# espduino-12-2.net
KiCad netlist of a schematic drawn in EAGLE
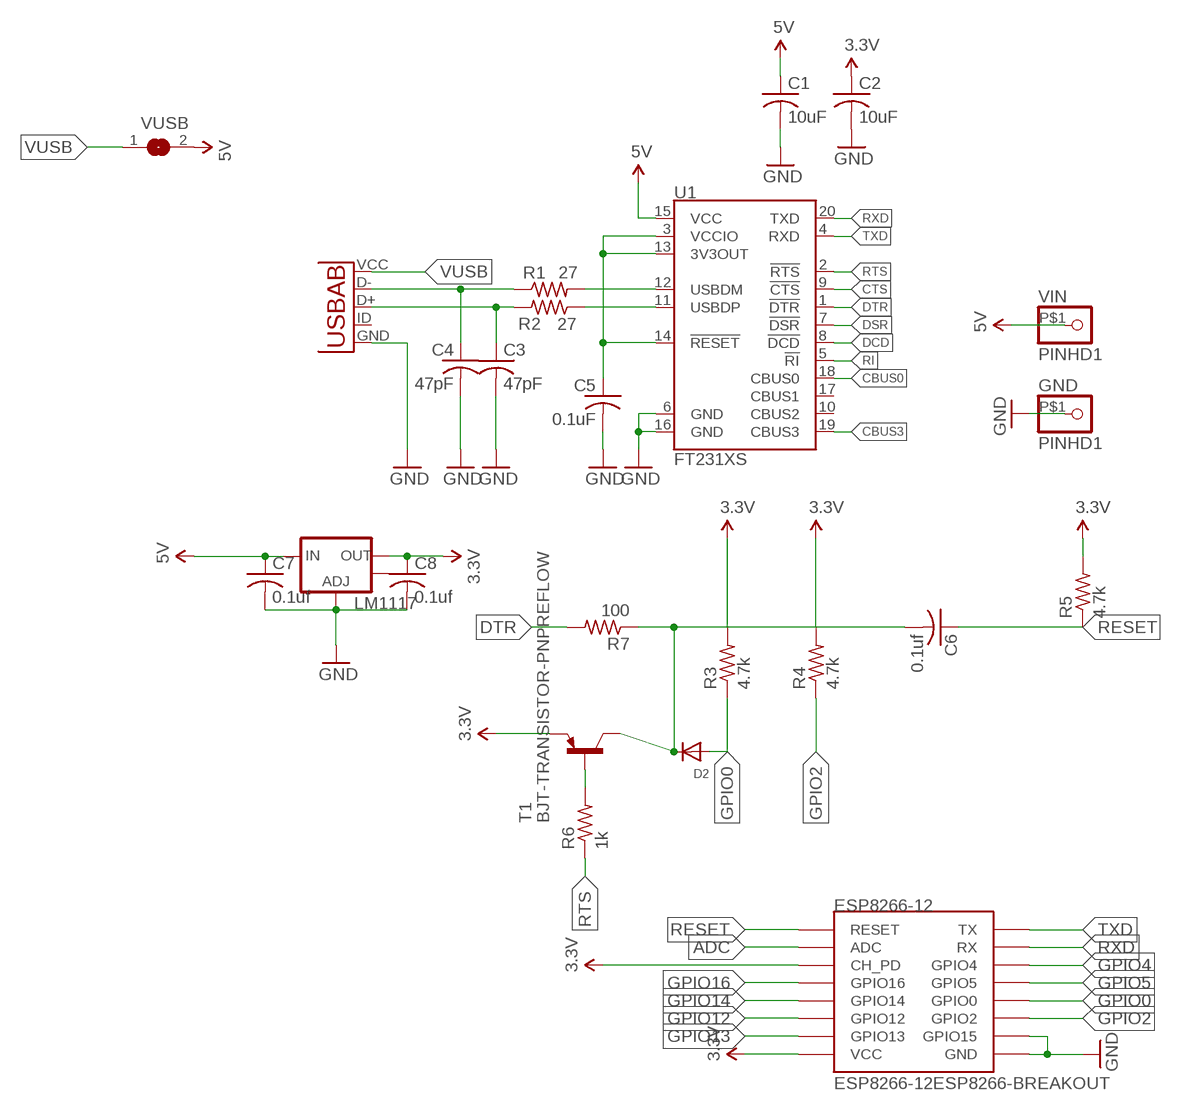
[diagram p0: schematic, sheet 1]

(export (version "E")
  (design (tool "Eeschema 10.0.6"))
  (components
    (comp (ref "C1")
      (value "10uF")
      (footprint "eagle-import:C0603")
      (libsource (lib "eagle-import") (part "C-USC0603"))
    )
    (comp (ref "C2")
      (value "10uF")
      (footprint "eagle-import:C0603")
      (libsource (lib "eagle-import") (part "C-USC0603"))
    )
    (comp (ref "C3")
      (value "47pF")
      (footprint "eagle-import:C0603")
      (libsource (lib "eagle-import") (part "C-USC0603"))
    )
    (comp (ref "C4")
      (value "47pF")
      (footprint "eagle-import:C0603")
      (libsource (lib "eagle-import") (part "C-USC0603"))
    )
    (comp (ref "C5")
      (value "0.1uF")
      (footprint "eagle-import:C0603")
      (libsource (lib "eagle-import") (part "C-USC0603"))
    )
    (comp (ref "C6")
      (value "0.1uf")
      (footprint "eagle-import:C0603")
      (libsource (lib "eagle-import") (part "C-USC0603"))
    )
    (comp (ref "C7")
      (value "0.1uf")
      (footprint "eagle-import:C0603")
      (libsource (lib "eagle-import") (part "C-USC0603"))
    )
    (comp (ref "C8")
      (value "0.1uf")
      (footprint "eagle-import:C0603")
      (libsource (lib "eagle-import") (part "C-USC0603"))
    )
    (comp (ref "D2")
      (value "DIODESOT23_REFLOW")
      (footprint "eagle-import:SOT23-R")
      (libsource (lib "eagle-import") (part "DIODESOT23_REFLOW"))
    )
    (comp (ref "ESP8266-12")
      (value "ESP8266-12ESP8266-BREAKOUT")
      (footprint "eagle-import:ESP8266-12-EXT-HEADERS")
      (libsource (lib "eagle-import") (part "ESP8266-12ESP8266-BREAKOUT"))
    )
    (comp (ref "GND")
      (value "PINHD1")
      (footprint "eagle-import:PINHD1")
      (libsource (lib "eagle-import") (part "PINHD1"))
    )
    (comp (ref "LM1117")
      (value "V_REG_LM1117SOT223")
      (footprint "eagle-import:SOT223")
      (libsource (lib "eagle-import") (part "V_REG_LM1117SOT223"))
    )
    (comp (ref "R1")
      (value "27")
      (footprint "eagle-import:R0603")
      (libsource (lib "eagle-import") (part "R-US_R0603"))
    )
    (comp (ref "R2")
      (value "27")
      (footprint "eagle-import:R0603")
      (libsource (lib "eagle-import") (part "R-US_R0603"))
    )
    (comp (ref "R3")
      (value "4.7k")
      (footprint "eagle-import:R0603")
      (libsource (lib "eagle-import") (part "R-US_R0603"))
    )
    (comp (ref "R4")
      (value "4.7k")
      (footprint "eagle-import:R0603")
      (libsource (lib "eagle-import") (part "R-US_R0603"))
    )
    (comp (ref "R5")
      (value "4.7k")
      (footprint "eagle-import:R0603")
      (libsource (lib "eagle-import") (part "R-US_R0603"))
    )
    (comp (ref "R6")
      (value "1k")
      (footprint "eagle-import:R0603")
      (libsource (lib "eagle-import") (part "R-US_R0603"))
    )
    (comp (ref "R7")
      (value "100")
      (footprint "eagle-import:R0603")
      (libsource (lib "eagle-import") (part "R-US_R0603"))
    )
    (comp (ref "T1")
      (value "BJT-TRANSISTOR-PNPREFLOW")
      (footprint "eagle-import:SOT23-R")
      (libsource (lib "eagle-import") (part "BJT-TRANSISTOR-PNPREFLOW"))
    )
    (comp (ref "U1")
      (value "FT231XS")
      (footprint "eagle-import:SSOP20_L")
      (libsource (lib "eagle-import") (part "FT231XS"))
    )
    (comp (ref "U2")
      (value "USB-AB")
      (footprint "eagle-import:MICRO-USB-A01SB141B1")
      (libsource (lib "eagle-import") (part "USB-AB"))
    )
    (comp (ref "VIN")
      (value "PINHD1")
      (footprint "eagle-import:PINHD1")
      (libsource (lib "eagle-import") (part "PINHD1"))
    )
    (comp (ref "VUSB")
      (value "SJCUTTABLE")
      (footprint "eagle-import:SJ-CUTTABLE")
      (libsource (lib "eagle-import") (part "SJCUTTABLE"))
    )
  )
  (nets
    (net (code "1") (name "3.3V") (class "Default")
      (node (ref "C2") (pin "1") (pinfunction "1_1") (pintype "passive"))
      (node (ref "C8") (pin "1") (pinfunction "1_1") (pintype "passive"))
      (node (ref "ESP8266-12") (pin "CH_PD") (pinfunction "CH_PD_CH_PD") (pintype "bidirectional"))
      (node (ref "ESP8266-12") (pin "VCC") (pinfunction "VCC_VCC") (pintype "bidirectional"))
      (node (ref "ESP8266-12") (pin "VCC_P") (pinfunction "VCC_VCC_P") (pintype "bidirectional"))
      (node (ref "LM1117") (pin "2") (pinfunction "OUT_2") (pintype "output"))
      (node (ref "R3") (pin "2") (pinfunction "2_2") (pintype "passive"))
      (node (ref "R4") (pin "2") (pinfunction "2_2") (pintype "passive"))
      (node (ref "R5") (pin "2") (pinfunction "2_2") (pintype "passive"))
      (node (ref "T1") (pin "2") (pinfunction "E_2") (pintype "passive"))
    )
    (net (code "2") (name "5V") (class "Default")
      (node (ref "C1") (pin "1") (pinfunction "1_1") (pintype "passive"))
      (node (ref "C7") (pin "1") (pinfunction "1_1") (pintype "passive"))
      (node (ref "LM1117") (pin "3") (pinfunction "IN_3") (pintype "input"))
      (node (ref "U1") (pin "15") (pinfunction "VCC_15") (pintype "bidirectional"))
      (node (ref "VIN") (pin "P$1") (pinfunction "GND_P$1") (pintype "passive"))
      (node (ref "VUSB") (pin "2") (pinfunction "2_2") (pintype "passive"))
    )
    (net (code "3") (name "ADC") (class "Default")
      (node (ref "ESP8266-12") (pin "ADC") (pinfunction "ADC_ADC") (pintype "bidirectional"))
      (node (ref "ESP8266-12") (pin "ADC_P") (pinfunction "ADC_ADC_P") (pintype "bidirectional"))
    )
    (net (code "4") (name "CBUS0") (class "Default")
      (node (ref "U1") (pin "18") (pinfunction "CBUS0_18") (pintype "bidirectional"))
    )
    (net (code "5") (name "CBUS3") (class "Default")
      (node (ref "U1") (pin "19") (pinfunction "CBUS3_19") (pintype "bidirectional"))
    )
    (net (code "6") (name "CTS") (class "Default")
      (node (ref "U1") (pin "9") (pinfunction "~{CTS}_9") (pintype "bidirectional"))
    )
    (net (code "7") (name "DCD") (class "Default")
      (node (ref "U1") (pin "8") (pinfunction "~{DCD}_8") (pintype "bidirectional"))
    )
    (net (code "8") (name "DSR") (class "Default")
      (node (ref "U1") (pin "7") (pinfunction "~{DSR}_7") (pintype "bidirectional"))
    )
    (net (code "9") (name "DTR") (class "Default")
      (node (ref "R7") (pin "2") (pinfunction "2_2") (pintype "passive"))
      (node (ref "U1") (pin "1") (pinfunction "~{DTR}_1") (pintype "bidirectional"))
    )
    (net (code "10") (name "GND") (class "Default")
      (node (ref "C1") (pin "2") (pinfunction "2_2") (pintype "passive"))
      (node (ref "C2") (pin "2") (pinfunction "2_2") (pintype "passive"))
      (node (ref "C3") (pin "2") (pinfunction "2_2") (pintype "passive"))
      (node (ref "C4") (pin "2") (pinfunction "2_2") (pintype "passive"))
      (node (ref "C5") (pin "2") (pinfunction "2_2") (pintype "passive"))
      (node (ref "C7") (pin "2") (pinfunction "2_2") (pintype "passive"))
      (node (ref "C8") (pin "2") (pinfunction "2_2") (pintype "passive"))
      (node (ref "ESP8266-12") (pin "GND") (pinfunction "GND_GND") (pintype "bidirectional"))
      (node (ref "ESP8266-12") (pin "GND_P") (pinfunction "GND_GND_P") (pintype "bidirectional"))
      (node (ref "ESP8266-12") (pin "GPIO15") (pinfunction "GPIO15_GPIO15") (pintype "bidirectional"))
      (node (ref "GND") (pin "P$1") (pinfunction "GND_P$1") (pintype "passive"))
      (node (ref "LM1117") (pin "1") (pinfunction "ADJ_1") (pintype "input"))
      (node (ref "U1") (pin "16") (pinfunction "GND_16") (pintype "bidirectional"))
      (node (ref "U1") (pin "6") (pinfunction "GND_6") (pintype "bidirectional"))
      (node (ref "U2") (pin "GND") (pinfunction "GND_GND") (pintype "bidirectional"))
    )
    (net (code "11") (name "GPIO0") (class "Default")
      (node (ref "D2") (pin "1") (pinfunction "A_1") (pintype "passive"))
      (node (ref "ESP8266-12") (pin "GPIO0") (pinfunction "GPIO0_GPIO0") (pintype "bidirectional"))
      (node (ref "ESP8266-12") (pin "GPIO0_P") (pinfunction "GPIO0_GPIO0_P") (pintype "bidirectional"))
      (node (ref "R3") (pin "1") (pinfunction "1_1") (pintype "passive"))
    )
    (net (code "12") (name "GPIO2") (class "Default")
      (node (ref "ESP8266-12") (pin "GPIO2") (pinfunction "GPIO2_GPIO2") (pintype "bidirectional"))
      (node (ref "ESP8266-12") (pin "GPIO2_P") (pinfunction "GPIO2_GPIO2_P") (pintype "bidirectional"))
      (node (ref "R4") (pin "1") (pinfunction "1_1") (pintype "passive"))
    )
    (net (code "13") (name "GPIO4") (class "Default")
      (node (ref "ESP8266-12") (pin "GPIO4") (pinfunction "GPIO4_GPIO4") (pintype "bidirectional"))
      (node (ref "ESP8266-12") (pin "GPIO4_P") (pinfunction "GPIO4_GPIO4_P") (pintype "bidirectional"))
    )
    (net (code "14") (name "GPIO5") (class "Default")
      (node (ref "ESP8266-12") (pin "GPIO5") (pinfunction "GPIO5_GPIO5") (pintype "bidirectional"))
      (node (ref "ESP8266-12") (pin "GPIO5_P") (pinfunction "GPIO5_GPIO5_P") (pintype "bidirectional"))
    )
    (net (code "15") (name "GPIO12") (class "Default")
      (node (ref "ESP8266-12") (pin "GPIO12") (pinfunction "GPIO12_GPIO12") (pintype "bidirectional"))
      (node (ref "ESP8266-12") (pin "GPIO12_P") (pinfunction "GPIO12_GPIO12_P") (pintype "bidirectional"))
    )
    (net (code "16") (name "GPIO13") (class "Default")
      (node (ref "ESP8266-12") (pin "GPIO13") (pinfunction "GPIO13_GPIO13") (pintype "bidirectional"))
      (node (ref "ESP8266-12") (pin "GPIO13_P") (pinfunction "GPIO13_GPIO13_P") (pintype "bidirectional"))
    )
    (net (code "17") (name "GPIO14") (class "Default")
      (node (ref "ESP8266-12") (pin "GPIO14") (pinfunction "GPIO14_GPIO14") (pintype "bidirectional"))
      (node (ref "ESP8266-12") (pin "GPIO14_P") (pinfunction "GPIO14_GPIO14_P") (pintype "bidirectional"))
    )
    (net (code "18") (name "GPIO16") (class "Default")
      (node (ref "ESP8266-12") (pin "GPIO16") (pinfunction "GPIO16_GPIO16") (pintype "bidirectional"))
      (node (ref "ESP8266-12") (pin "GPIO_16_P") (pinfunction "GPIO16_GPIO_16_P") (pintype "bidirectional"))
    )
    (net (code "19") (name "Net-(C3-Pad1)") (class "Default")
      (node (ref "C3") (pin "1") (pinfunction "1_1") (pintype "passive"))
      (node (ref "R2") (pin "2") (pinfunction "2_2") (pintype "passive"))
      (node (ref "U2") (pin "D+") (pinfunction "D+_D+") (pintype "bidirectional"))
    )
    (net (code "20") (name "Net-(C4-Pad1)") (class "Default")
      (node (ref "C4") (pin "1") (pinfunction "1_1") (pintype "passive"))
      (node (ref "R1") (pin "1") (pinfunction "1_1") (pintype "passive"))
      (node (ref "U2") (pin "D-") (pinfunction "D-_D-") (pintype "bidirectional"))
    )
    (net (code "21") (name "Net-(D2-C)") (class "Default")
      (node (ref "C6") (pin "2") (pinfunction "2_2") (pintype "passive"))
      (node (ref "D2") (pin "3") (pinfunction "C_3") (pintype "passive"))
      (node (ref "R7") (pin "1") (pinfunction "1_1") (pintype "passive"))
      (node (ref "T1") (pin "3") (pinfunction "C_3") (pintype "passive"))
    )
    (net (code "22") (name "Net-(T1-B)") (class "Default")
      (node (ref "R6") (pin "2") (pinfunction "2_2") (pintype "passive"))
      (node (ref "T1") (pin "1") (pinfunction "B_1") (pintype "passive"))
    )
    (net (code "23") (name "Net-(U1-3V3OUT)") (class "Default")
      (node (ref "C5") (pin "1") (pinfunction "1_1") (pintype "passive"))
      (node (ref "U1") (pin "13") (pinfunction "3V3OUT_13") (pintype "bidirectional"))
      (node (ref "U1") (pin "14") (pinfunction "~{RESET}_14") (pintype "bidirectional"))
      (node (ref "U1") (pin "3") (pinfunction "VCCIO_3") (pintype "bidirectional"))
    )
    (net (code "24") (name "Net-(U1-USBDM)") (class "Default")
      (node (ref "R1") (pin "2") (pinfunction "2_2") (pintype "passive"))
      (node (ref "U1") (pin "12") (pinfunction "USBDM_12") (pintype "bidirectional"))
    )
    (net (code "25") (name "Net-(U1-USBDP)") (class "Default")
      (node (ref "R2") (pin "1") (pinfunction "1_1") (pintype "passive"))
      (node (ref "U1") (pin "11") (pinfunction "USBDP_11") (pintype "bidirectional"))
    )
    (net (code "26") (name "RESET") (class "Default")
      (node (ref "C6") (pin "1") (pinfunction "1_1") (pintype "passive"))
      (node (ref "ESP8266-12") (pin "RESET") (pinfunction "RESET_RESET") (pintype "bidirectional"))
      (node (ref "ESP8266-12") (pin "RST_P") (pinfunction "RESET_RST_P") (pintype "bidirectional"))
      (node (ref "R5") (pin "1") (pinfunction "1_1") (pintype "passive"))
    )
    (net (code "27") (name "RI") (class "Default")
      (node (ref "U1") (pin "5") (pinfunction "~{RI}_5") (pintype "bidirectional"))
    )
    (net (code "28") (name "RTS") (class "Default")
      (node (ref "R6") (pin "1") (pinfunction "1_1") (pintype "passive"))
      (node (ref "U1") (pin "2") (pinfunction "~{RTS}_2") (pintype "bidirectional"))
    )
    (net (code "29") (name "RXD") (class "Default")
      (node (ref "ESP8266-12") (pin "RX") (pinfunction "RX_RX") (pintype "bidirectional"))
      (node (ref "ESP8266-12") (pin "RX_P") (pinfunction "RX_RX_P") (pintype "bidirectional"))
      (node (ref "U1") (pin "20") (pinfunction "TXD_20") (pintype "bidirectional"))
    )
    (net (code "30") (name "TXD") (class "Default")
      (node (ref "ESP8266-12") (pin "TX") (pinfunction "TX_TX") (pintype "bidirectional"))
      (node (ref "ESP8266-12") (pin "TX_P") (pinfunction "TX_TX_P") (pintype "bidirectional"))
      (node (ref "U1") (pin "4") (pinfunction "RXD_4") (pintype "bidirectional"))
    )
    (net (code "31") (name "VUSB") (class "Default")
      (node (ref "U2") (pin "VCC") (pinfunction "VBUS_VCC") (pintype "bidirectional"))
      (node (ref "VUSB") (pin "1") (pinfunction "1_1") (pintype "passive"))
    )
    (net (code "32") (name "unconnected-(LM1117-OUT-Pad4)") (class "Default")
      (node (ref "LM1117") (pin "4") (pinfunction "OUT_4") (pintype "output"))
    )
    (net (code "33") (name "unconnected-(U1-CBUS1-Pad17)") (class "Default")
      (node (ref "U1") (pin "17") (pinfunction "CBUS1_17") (pintype "bidirectional"))
    )
    (net (code "34") (name "unconnected-(U1-CBUS2-Pad10)") (class "Default")
      (node (ref "U1") (pin "10") (pinfunction "CBUS2_10") (pintype "bidirectional"))
    )
    (net (code "35") (name "unconnected-(U2-USBID-PadID)") (class "Default")
      (node (ref "U2") (pin "ID") (pinfunction "USBID_ID") (pintype "bidirectional"))
    )
  )
)
